# Coils.net
KiCad netlist of a schematic drawn in Altium Designer
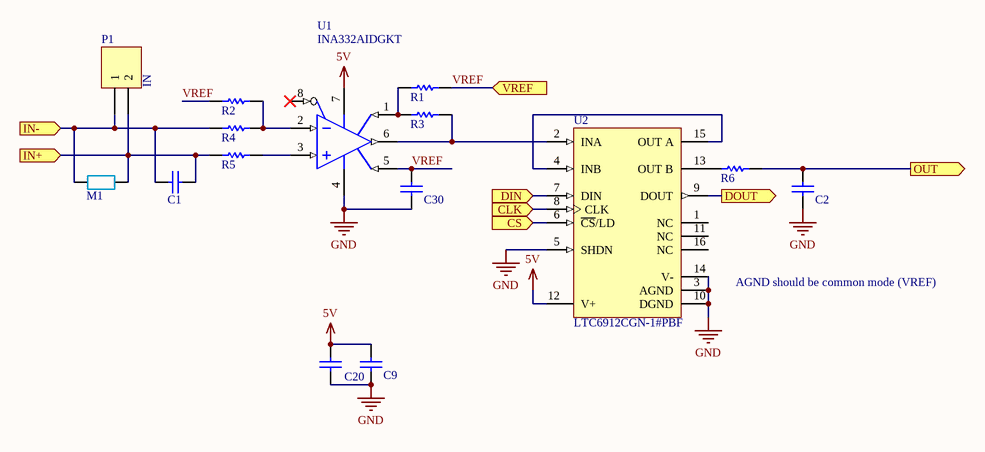
[diagram p0: Coils.SchDoc]

(export (version "E")
  (design (tool "Eeschema 10.0.6"))
  (components
    (comp (ref "C1")
      (value "CAP 25V 0402(1005)")
      (footprint "CAPC0402(1005)60_N")
      (description "CAP 25V ±1% 0402 (1005 Metric) Thickness 0.6mm SMD")
      (fields (field (name "TOLERANCE") "±1%"))
      (libsource (lib "Altium Content Vault") (part "CMP-1034-00714-1"))
    )
    (comp (ref "C2")
      (value "CAP 100pF 25V 0402(1005)")
      (footprint "CAPC0402(1005)60_N")
      (description "CAP 100pF 25V ±1% 0402 (1005 Metric) Thickness 0.6mm SMD")
      (fields (field (name "TOLERANCE") "±1%"))
      (libsource (lib "Altium Content Vault") (part "CAP"))
    )
    (comp (ref "C9")
      (value "CAP 100nF 25V 0402(1005)")
      (footprint "CAPC0402(1005)60_N")
      (description "CAP 100nF 25V ±20% 0402 (1005 Metric) Thickness 0.6mm SMD")
      (fields (field (name "TOLERANCE") "±20%"))
      (libsource (lib "Altium Content Vault") (part "CMP-1034-02073-1"))
    )
    (comp (ref "C20")
      (value "CAP 100nF 25V 0402(1005)")
      (footprint "CAPC0402(1005)60_N")
      (description "CAP 100nF 25V ±20% 0402 (1005 Metric) Thickness 0.6mm SMD")
      (fields (field (name "TOLERANCE") "±20%"))
      (libsource (lib "Altium Content Vault") (part "CMP-1034-02073-1"))
    )
    (comp (ref "C30")
      (value "CAP 100nF 25V 0402(1005)")
      (footprint "CAPC0402(1005)60_N")
      (description "CAP 100nF 25V ±20% 0402 (1005 Metric) Thickness 0.6mm SMD")
      (fields (field (name "TOLERANCE") "±20%"))
      (libsource (lib "Altium Content Vault") (part "CMP-1034-02073-1"))
    )
    (comp (ref "M1") (value "Multi Footprint") (footprint "MULTI") (libsource (lib "Centum") (part "Multi")))
    (comp (ref "P1")
      (value "IN")
      (footprint "HDR1X2")
      (description "Header, 2-Pin")
      (fields (field (name "PUBLISHER") "Altium Limited"))
      (libsource (lib "Miscellaneous Connectors") (part "Header 2"))
    )
    (comp (ref "R1")
      (value "220R 1% 0402(1005)")
      (footprint "RESC0402(1005)_N")
      (description "220R 0.063W 1% 0402 (1005 Metric)  SMD")
      (fields (field (name "TOLERANCE") "1 %") (field (name "POWER") "0.063 W"))
      (libsource (lib "Altium Content Vault") (part "CMP-1011-00433-1"))
    )
    (comp (ref "R2")
      (value "10K 1% 0402(1005)")
      (footprint "RESC0402(1005)_N")
      (description "10K 0.063W 1% 0402 (1005 Metric)  SMD")
      (fields (field (name "TOLERANCE") "1 %") (field (name "POWER") "0.063 W"))
      (libsource (lib "Altium Content Vault") (part "CMP-1011-00623-1"))
    )
    (comp (ref "R3")
      (value "2K 1% 0402(1005)")
      (footprint "RESC0402(1005)_N")
      (description "2K 0.063W 1% 0402 (1005 Metric)  SMD")
      (fields (field (name "POWER") "0.063 W") (field (name "TOLERANCE") "1 %"))
      (libsource (lib "Altium Content Vault") (part "CMP-1011-00542-1"))
    )
    (comp (ref "R4")
      (value "10K 1% 0402(1005)")
      (footprint "RESC0402(1005)_N")
      (description "10K 0.063W 1% 0402 (1005 Metric)  SMD")
      (fields (field (name "TOLERANCE") "1 %") (field (name "POWER") "0.063 W"))
      (libsource (lib "Altium Content Vault") (part "CMP-1011-00623-1"))
    )
    (comp (ref "R5")
      (value "10K 1% 0402(1005)")
      (footprint "RESC0402(1005)_N")
      (description "10K 0.063W 1% 0402 (1005 Metric)  SMD")
      (fields (field (name "TOLERANCE") "1 %") (field (name "POWER") "0.063 W"))
      (libsource (lib "Altium Content Vault") (part "CMP-1011-00623-1"))
    )
    (comp (ref "R6")
      (value "10K 1% 0402(1005)")
      (footprint "RESC0402(1005)_N")
      (description "10K 0.063W 1% 0402 (1005 Metric)  SMD")
      (fields (field (name "TOLERANCE") "1 %") (field (name "POWER") "0.063 W"))
      (libsource (lib "Altium Content Vault") (part "CMP-1011-00623-1"))
    )
    (comp (ref "U1")
      (value "INA332AIDGKT")
      (footprint "TI-DGK8_N")
      (fields (field (name "MANUFACTURER") "Texas Instruments"))
      (libsource (lib "Altium Content Vault") (part "CMP-0944-00079-1"))
    )
    (comp (ref "U2")
      (value "LTC6912CGN-1#PBF")
      (footprint "LT-GN-16_N")
      (fields
        (field (name "MANUFACTURER") "Linear Technology")
        (field (name "LINEAR TECHNOLOGY PART NUMBER") "LTC6912-1")
      )
      (libsource (lib "Altium Content Vault") (part "CMP-0359-00187-2"))
    )
  )
  (nets
    (net (code "1") (name "/CLK") (class "Default")
      (node (ref "U2") (pin "8") (pinfunction "CLK_8") (pintype "input"))
    )
    (net (code "2") (name "/CS") (class "Default")
      (node (ref "U2") (pin "6") (pinfunction "~{CS}/LD_6") (pintype "input"))
    )
    (net (code "3") (name "/DIN") (class "Default")
      (node (ref "U2") (pin "7") (pinfunction "DIN_7") (pintype "input"))
    )
    (net (code "4") (name "/DOUT") (class "Default")
      (node (ref "U2") (pin "9") (pinfunction "DOUT_9") (pintype "output"))
    )
    (net (code "5") (name "/IN+") (class "Default")
      (node (ref "C1") (pin "2") (pinfunction "2_2") (pintype "passive"))
      (node (ref "M1") (pin "2") (pinfunction "2_2") (pintype "passive"))
      (node (ref "P1") (pin "2") (pinfunction "2_2") (pintype "passive"))
      (node (ref "R5") (pin "1") (pinfunction "1_1") (pintype "passive"))
    )
    (net (code "6") (name "/IN-") (class "Default")
      (node (ref "C1") (pin "1") (pinfunction "1_1") (pintype "passive"))
      (node (ref "M1") (pin "1") (pinfunction "1_1") (pintype "passive"))
      (node (ref "P1") (pin "1") (pinfunction "1_1") (pintype "passive"))
      (node (ref "R4") (pin "1") (pinfunction "1_1") (pintype "passive"))
    )
    (net (code "7") (name "/OUT") (class "Default")
      (node (ref "C2") (pin "2") (pinfunction "2_2") (pintype "passive"))
      (node (ref "R6") (pin "1") (pinfunction "1_1") (pintype "passive"))
    )
    (net (code "8") (name "/VREF") (class "Default")
      (node (ref "C30") (pin "2") (pinfunction "2_2") (pintype "passive"))
      (node (ref "R1") (pin "2") (pinfunction "2_2") (pintype "passive"))
      (node (ref "R2") (pin "1") (pinfunction "1_1") (pintype "passive"))
      (node (ref "U1") (pin "5") (pinfunction "REF_5") (pintype "input"))
    )
    (net (code "9") (name "5V") (class "Default")
      (node (ref "C20") (pin "2") (pinfunction "2_2") (pintype "passive"))
      (node (ref "C9") (pin "2") (pinfunction "2_2") (pintype "passive"))
      (node (ref "U1") (pin "7") (pinfunction "V+_7") (pintype "power_in"))
      (node (ref "U2") (pin "12") (pinfunction "V+_12") (pintype "power_in"))
    )
    (net (code "10") (name "GND") (class "Default")
      (node (ref "C2") (pin "1") (pinfunction "1_1") (pintype "passive"))
      (node (ref "C20") (pin "1") (pinfunction "1_1") (pintype "passive"))
      (node (ref "C30") (pin "1") (pinfunction "1_1") (pintype "passive"))
      (node (ref "C9") (pin "1") (pinfunction "1_1") (pintype "passive"))
      (node (ref "U1") (pin "4") (pinfunction "V-_4") (pintype "power_in"))
      (node (ref "U2") (pin "10") (pinfunction "DGND_10") (pintype "power_in"))
      (node (ref "U2") (pin "14") (pinfunction "V-_14") (pintype "power_in"))
      (node (ref "U2") (pin "3") (pinfunction "AGND_3") (pintype "power_in"))
      (node (ref "U2") (pin "5") (pinfunction "SHDN_5") (pintype "input"))
    )
    (net (code "11") (name "Net-(U1-RG)") (class "Default")
      (node (ref "R1") (pin "1") (pinfunction "1_1") (pintype "passive"))
      (node (ref "R3") (pin "1") (pinfunction "1_1") (pintype "passive"))
      (node (ref "U1") (pin "1") (pinfunction "RG_1") (pintype "input"))
    )
    (net (code "12") (name "Net-(U1-VIN+)") (class "Default")
      (node (ref "R5") (pin "2") (pinfunction "2_2") (pintype "passive"))
      (node (ref "U1") (pin "3") (pinfunction "VIN+_3") (pintype "input"))
    )
    (net (code "13") (name "Net-(U1-VIN-)") (class "Default")
      (node (ref "R2") (pin "2") (pinfunction "2_2") (pintype "passive"))
      (node (ref "R4") (pin "2") (pinfunction "2_2") (pintype "passive"))
      (node (ref "U1") (pin "2") (pinfunction "VIN-_2") (pintype "input"))
    )
    (net (code "14") (name "Net-(U1-VOUT)") (class "Default")
      (node (ref "R3") (pin "2") (pinfunction "2_2") (pintype "passive"))
      (node (ref "U1") (pin "6") (pinfunction "VOUT_6") (pintype "output"))
      (node (ref "U2") (pin "2") (pinfunction "INA_2") (pintype "input"))
    )
    (net (code "15") (name "Net-(U2-INB)") (class "Default")
      (node (ref "U2") (pin "15") (pinfunction "OUT_A_15") (pintype "tri_state"))
      (node (ref "U2") (pin "4") (pinfunction "INB_4") (pintype "input"))
    )
    (net (code "16") (name "Net-(U2-OUT_B)") (class "Default")
      (node (ref "R6") (pin "2") (pinfunction "2_2") (pintype "passive"))
      (node (ref "U2") (pin "13") (pinfunction "OUT_B_13") (pintype "tri_state"))
    )
    (net (code "17") (name "unconnected-(U1-SHUTDOWN-Pad8)") (class "Default")
      (node (ref "U1") (pin "8") (pinfunction "SHUTDOWN_8") (pintype "input+no_connect"))
    )
    (net (code "18") (name "unconnected-(U2-NC-Pad1)") (class "Default")
      (node (ref "U2") (pin "1") (pinfunction "NC_1") (pintype "passive"))
    )
    (net (code "19") (name "unconnected-(U2-NC-Pad11)") (class "Default")
      (node (ref "U2") (pin "11") (pinfunction "NC_11") (pintype "passive"))
    )
    (net (code "20") (name "unconnected-(U2-NC-Pad16)") (class "Default")
      (node (ref "U2") (pin "16") (pinfunction "NC_16") (pintype "passive"))
    )
  )
)
